# pypl_v1_4.net
KiCad netlist of a schematic drawn in EAGLE
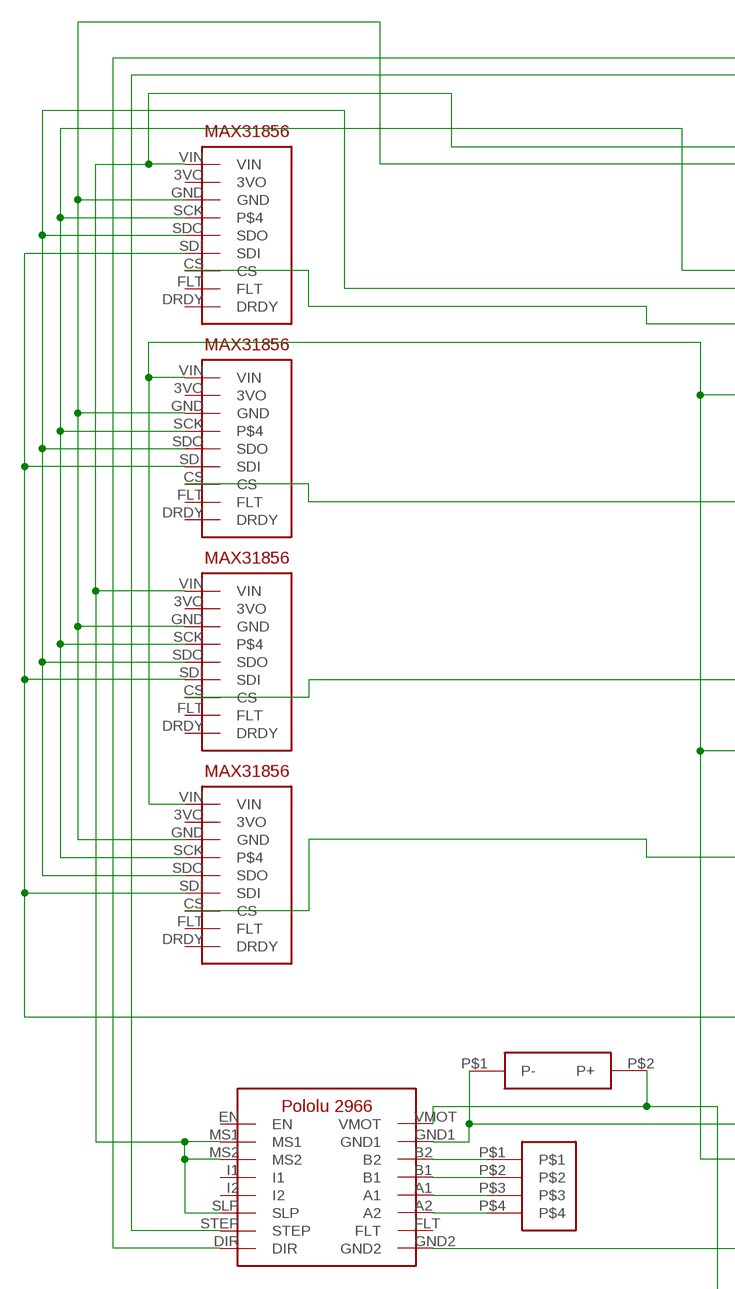
[diagram p0: schematic, sheet 1, part 1 of 2]
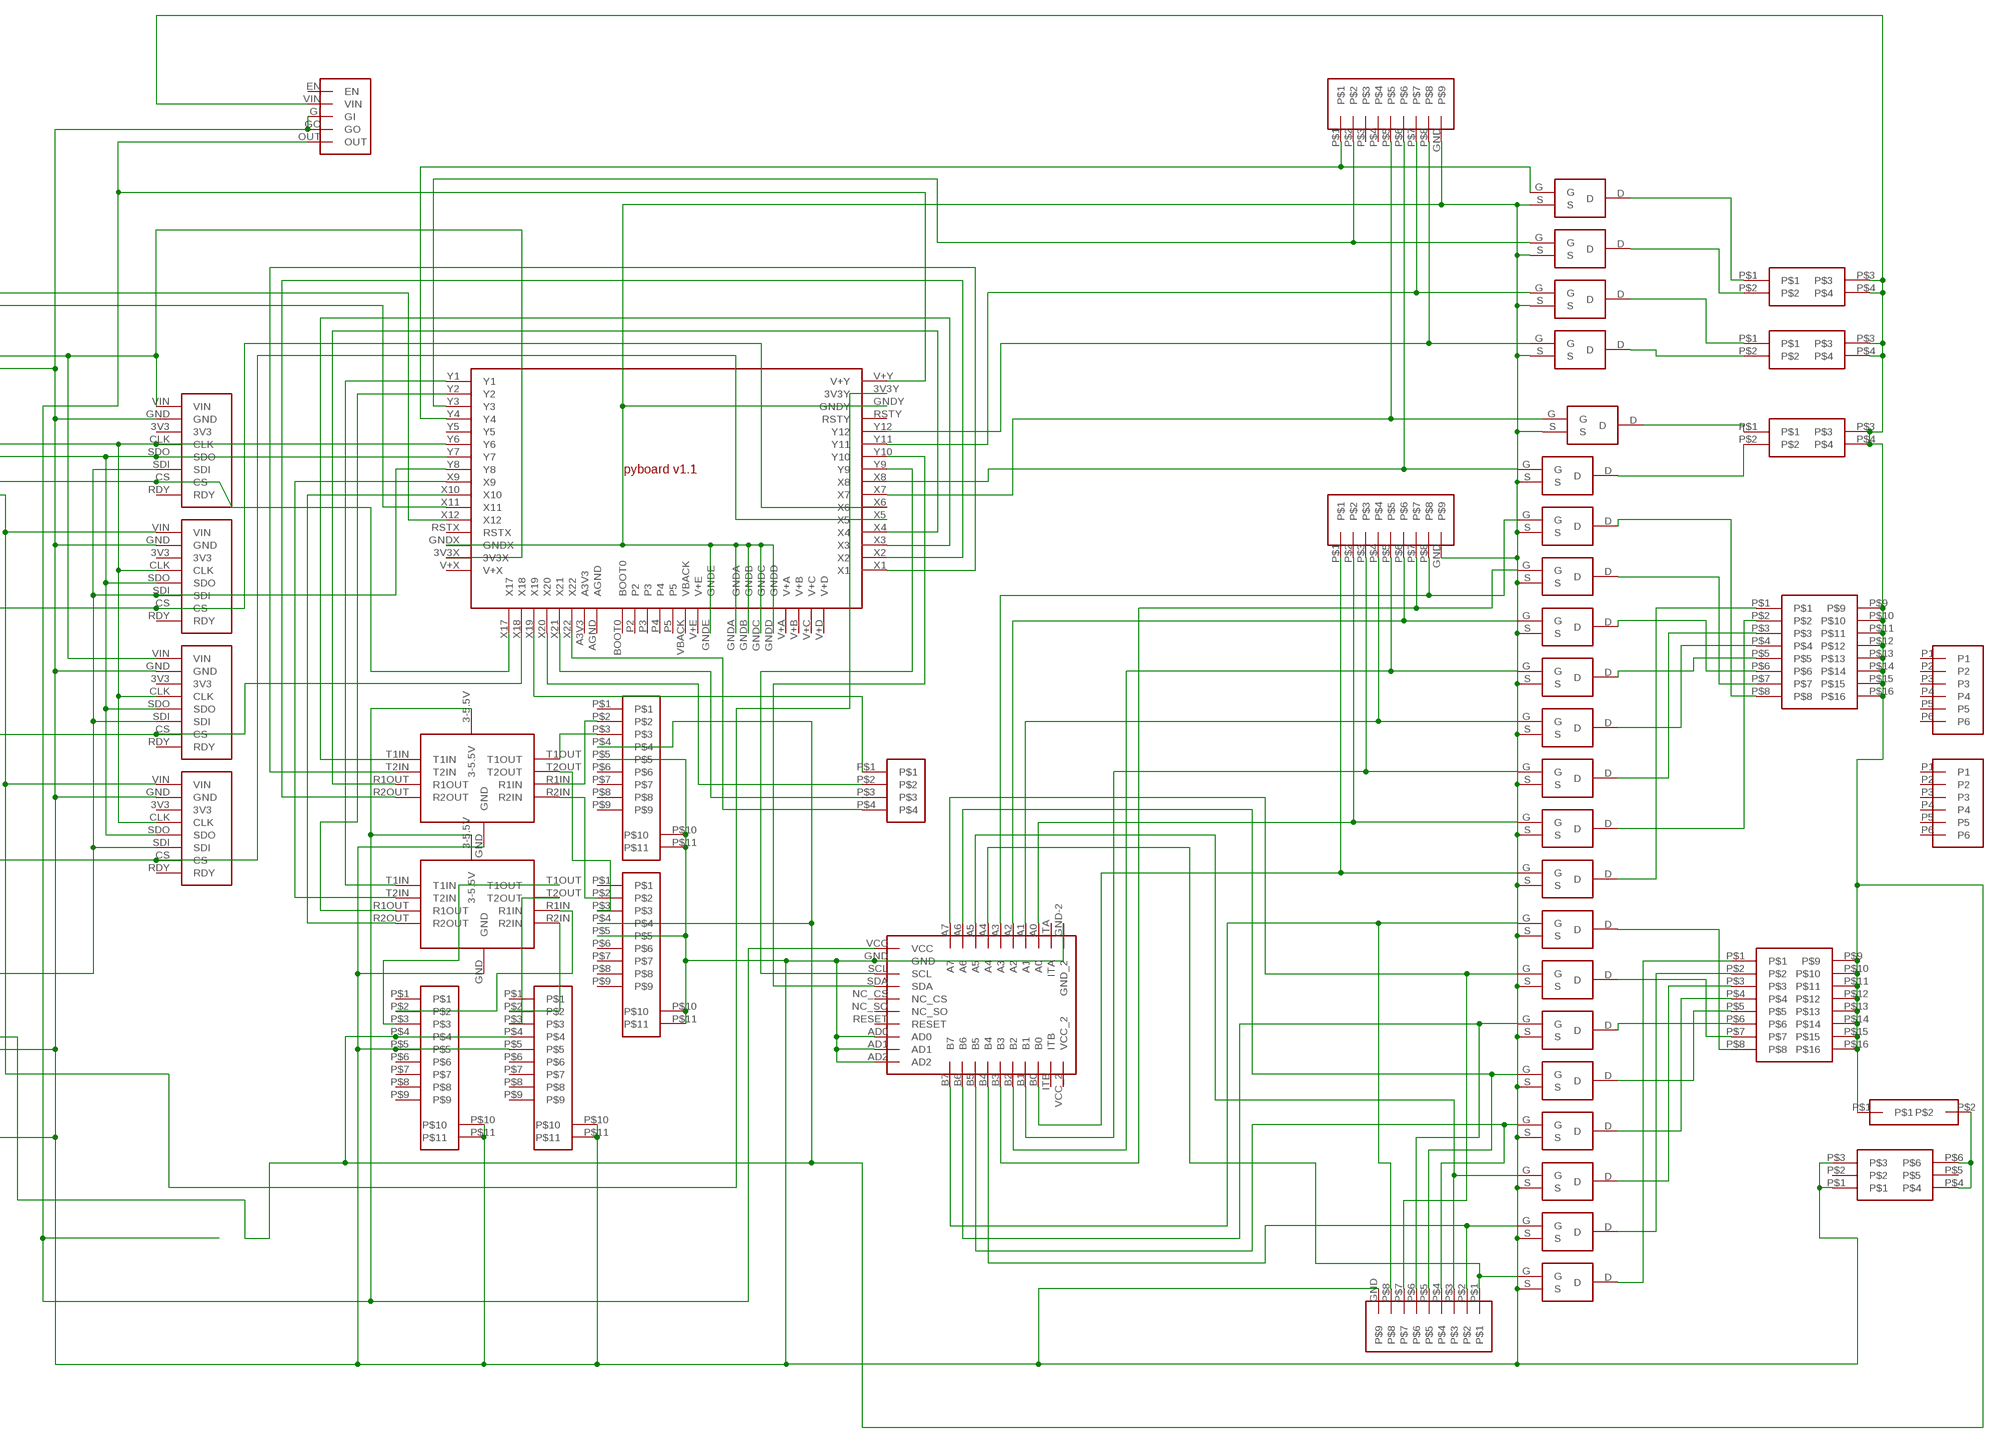
[diagram p1: schematic, sheet 1, part 2 of 2]

(export (version "E")
  (design (tool "Eeschema 10.0.6"))
  (components
    (comp (ref "U$1")
      (value "MAX31865")
      (footprint "eagle-import:MAX31865")
      (libsource (lib "eagle-import") (part "MAX31865"))
    )
    (comp (ref "U$2")
      (value "IRLB8721PBF")
      (footprint "eagle-import:IRLB8721PBF")
      (libsource (lib "eagle-import") (part "IRLB8721PBF"))
    )
    (comp (ref "U$3")
      (value "IRLB8721PBF")
      (footprint "eagle-import:IRLB8721PBF")
      (libsource (lib "eagle-import") (part "IRLB8721PBF"))
    )
    (comp (ref "U$4")
      (value "IRLB8721PBF")
      (footprint "eagle-import:IRLB8721PBF")
      (libsource (lib "eagle-import") (part "IRLB8721PBF"))
    )
    (comp (ref "U$5")
      (value "IRLB8721PBF")
      (footprint "eagle-import:IRLB8721PBF")
      (libsource (lib "eagle-import") (part "IRLB8721PBF"))
    )
    (comp (ref "U$6")
      (value "IRLB8721PBF")
      (footprint "eagle-import:IRLB8721PBF")
      (libsource (lib "eagle-import") (part "IRLB8721PBF"))
    )
    (comp (ref "U$7")
      (value "IRLB8721PBF")
      (footprint "eagle-import:IRLB8721PBF")
      (libsource (lib "eagle-import") (part "IRLB8721PBF"))
    )
    (comp (ref "U$8")
      (value "IRLB8721PBF")
      (footprint "eagle-import:IRLB8721PBF")
      (libsource (lib "eagle-import") (part "IRLB8721PBF"))
    )
    (comp (ref "U$9")
      (value "IRLB8721PBF")
      (footprint "eagle-import:IRLB8721PBF")
      (libsource (lib "eagle-import") (part "IRLB8721PBF"))
    )
    (comp (ref "U$10")
      (value "MCP23017")
      (footprint "eagle-import:MCP23017")
      (libsource (lib "eagle-import") (part "MCP23017"))
    )
    (comp (ref "U$11")
      (value "IRLB8721PBF")
      (footprint "eagle-import:IRLB8721PBF")
      (libsource (lib "eagle-import") (part "IRLB8721PBF"))
    )
    (comp (ref "U$12")
      (value "IRLB8721PBF")
      (footprint "eagle-import:IRLB8721PBF")
      (libsource (lib "eagle-import") (part "IRLB8721PBF"))
    )
    (comp (ref "U$13")
      (value "IRLB8721PBF")
      (footprint "eagle-import:IRLB8721PBF")
      (libsource (lib "eagle-import") (part "IRLB8721PBF"))
    )
    (comp (ref "U$14")
      (value "IRLB8721PBF")
      (footprint "eagle-import:IRLB8721PBF")
      (libsource (lib "eagle-import") (part "IRLB8721PBF"))
    )
    (comp (ref "U$15")
      (value "IRLB8721PBF")
      (footprint "eagle-import:IRLB8721PBF")
      (libsource (lib "eagle-import") (part "IRLB8721PBF"))
    )
    (comp (ref "U$16")
      (value "IRLB8721PBF")
      (footprint "eagle-import:IRLB8721PBF")
      (libsource (lib "eagle-import") (part "IRLB8721PBF"))
    )
    (comp (ref "U$17")
      (value "IRLB8721PBF")
      (footprint "eagle-import:IRLB8721PBF")
      (libsource (lib "eagle-import") (part "IRLB8721PBF"))
    )
    (comp (ref "U$18")
      (value "IRLB8721PBF")
      (footprint "eagle-import:IRLB8721PBF")
      (libsource (lib "eagle-import") (part "IRLB8721PBF"))
    )
    (comp (ref "U$19")
      (value "DSUB-9")
      (footprint "eagle-import:DSUB-9")
      (libsource (lib "eagle-import") (part "DSUB-9"))
    )
    (comp (ref "U$20")
      (value "DSUB-9")
      (footprint "eagle-import:DSUB-9")
      (libsource (lib "eagle-import") (part "DSUB-9"))
    )
    (comp (ref "U$21")
      (value "DSUB-9")
      (footprint "eagle-import:DSUB-9")
      (libsource (lib "eagle-import") (part "DSUB-9"))
    )
    (comp (ref "U$22")
      (value "DSUB-9")
      (footprint "eagle-import:DSUB-9")
      (libsource (lib "eagle-import") (part "DSUB-9"))
    )
    (comp (ref "U$23")
      (value "MAX31865")
      (footprint "eagle-import:MAX31865")
      (libsource (lib "eagle-import") (part "MAX31865"))
    )
    (comp (ref "U$24")
      (value "PYBOARD_V1.1")
      (footprint "eagle-import:PYBOARD_V1.1")
      (libsource (lib "eagle-import") (part "PYBOARD_V1.1"))
    )
    (comp (ref "U$25")
      (value "MAX31865")
      (footprint "eagle-import:MAX31865")
      (libsource (lib "eagle-import") (part "MAX31865"))
    )
    (comp (ref "U$26")
      (value "MAX31865")
      (footprint "eagle-import:MAX31865")
      (libsource (lib "eagle-import") (part "MAX31865"))
    )
    (comp (ref "U$27")
      (value "BORNIER_DUPLEX_X16")
      (footprint "eagle-import:BORNIER_DUPLEX_X16")
      (libsource (lib "eagle-import") (part "BORNIER_DUPLEX_X16"))
    )
    (comp (ref "U$28")
      (value "BORNIER_DUPLEX_X16")
      (footprint "eagle-import:BORNIER_DUPLEX_X16")
      (libsource (lib "eagle-import") (part "BORNIER_DUPLEX_X16"))
    )
    (comp (ref "U$29")
      (value "CAP-GOTRONIC-04936")
      (footprint "eagle-import:CAP-GOTRONIC-04936")
      (libsource (lib "eagle-import") (part "CAP-GOTRONIC-04936"))
    )
    (comp (ref "U$30")
      (value "BORNIER_1X4_2.54")
      (footprint "eagle-import:BORNIER_1X4_2.54")
      (libsource (lib "eagle-import") (part "BORNIER_1X4_2.54"))
    )
    (comp (ref "U$31")
      (value "PORTE-FUSIBLE")
      (footprint "eagle-import:PORTE-FUSIBLE")
      (libsource (lib "eagle-import") (part "PORTE-FUSIBLE"))
    )
    (comp (ref "U$32")
      (value "MP6500-2966")
      (footprint "eagle-import:MP6500-2966")
      (libsource (lib "eagle-import") (part "MP6500-2966"))
    )
    (comp (ref "U$33")
      (value "IRLB8721PBF")
      (footprint "eagle-import:IRLB8721PBF")
      (libsource (lib "eagle-import") (part "IRLB8721PBF"))
    )
    (comp (ref "U$34")
      (value "IRLB8721PBF")
      (footprint "eagle-import:IRLB8721PBF")
      (libsource (lib "eagle-import") (part "IRLB8721PBF"))
    )
    (comp (ref "U$35")
      (value "BORNIER_DUPLEX_X4")
      (footprint "eagle-import:BORNIER_DUPLEX_X4")
      (libsource (lib "eagle-import") (part "BORNIER_DUPLEX_X4"))
    )
    (comp (ref "U$36")
      (value "BOB-1189")
      (footprint "eagle-import:BOB-11189")
      (libsource (lib "eagle-import") (part "BOB-1189"))
    )
    (comp (ref "U$37")
      (value "BOB-1189")
      (footprint "eagle-import:BOB-11189")
      (libsource (lib "eagle-import") (part "BOB-1189"))
    )
    (comp (ref "U$38")
      (value "MOLEX_MINIFT_JR_ANGLED_X6")
      (footprint "eagle-import:MOLEX_MINIFT_JR_ANGLED_X6")
      (libsource (lib "eagle-import") (part "MOLEX_MINIFT_JR_ANGLED_X6"))
    )
    (comp (ref "U$39")
      (value "D24V50F5D24V50F5")
      (footprint "eagle-import:D24V50F5")
      (libsource (lib "eagle-import") (part "D24V50F5D24V50F5"))
    )
    (comp (ref "U$40")
      (value "BORNIER_DUPLEX_X4")
      (footprint "eagle-import:BORNIER_DUPLEX_X4")
      (libsource (lib "eagle-import") (part "BORNIER_DUPLEX_X4"))
    )
    (comp (ref "U$41")
      (value "BORNIER_DUPLEX_X4")
      (footprint "eagle-import:BORNIER_DUPLEX_X4")
      (libsource (lib "eagle-import") (part "BORNIER_DUPLEX_X4"))
    )
    (comp (ref "U$42")
      (value "IRLB8721PBF")
      (footprint "eagle-import:IRLB8721PBF")
      (libsource (lib "eagle-import") (part "IRLB8721PBF"))
    )
    (comp (ref "U$43")
      (value "IRLB8721PBF")
      (footprint "eagle-import:IRLB8721PBF")
      (libsource (lib "eagle-import") (part "IRLB8721PBF"))
    )
    (comp (ref "U$44")
      (value "IRLB8721PBF")
      (footprint "eagle-import:IRLB8721PBF")
      (libsource (lib "eagle-import") (part "IRLB8721PBF"))
    )
    (comp (ref "U$45")
      (value "IRLB8721PBF")
      (footprint "eagle-import:IRLB8721PBF")
      (libsource (lib "eagle-import") (part "IRLB8721PBF"))
    )
    (comp (ref "U$46")
      (value "BORNIER_1X4_2.54")
      (footprint "eagle-import:BORNIER_1X4_2.54")
      (libsource (lib "eagle-import") (part "BORNIER_1X4_2.54"))
    )
    (comp (ref "U$47")
      (value "RESISTOR_BANK_BUSSED_X8")
      (footprint "eagle-import:RESISTOR_BANK_BUSSED_X8")
      (libsource (lib "eagle-import") (part "RESISTOR_BANK_BUSSED_X8"))
    )
    (comp (ref "U$48")
      (value "RESISTOR_BANK_BUSSED_X8")
      (footprint "eagle-import:RESISTOR_BANK_BUSSED_X8")
      (libsource (lib "eagle-import") (part "RESISTOR_BANK_BUSSED_X8"))
    )
    (comp (ref "U$49")
      (value "RESISTOR_BANK_BUSSED_X8")
      (footprint "eagle-import:RESISTOR_BANK_BUSSED_X8")
      (libsource (lib "eagle-import") (part "RESISTOR_BANK_BUSSED_X8"))
    )
    (comp (ref "U$50")
      (value "MAX31856")
      (footprint "eagle-import:MAX31856")
      (libsource (lib "eagle-import") (part "MAX31856"))
    )
    (comp (ref "U$51")
      (value "MAX31856")
      (footprint "eagle-import:MAX31856")
      (libsource (lib "eagle-import") (part "MAX31856"))
    )
    (comp (ref "U$52")
      (value "MAX31856")
      (footprint "eagle-import:MAX31856")
      (libsource (lib "eagle-import") (part "MAX31856"))
    )
    (comp (ref "U$53")
      (value "MAX31856")
      (footprint "eagle-import:MAX31856")
      (libsource (lib "eagle-import") (part "MAX31856"))
    )
    (comp (ref "U$54")
      (value "PINH06")
      (footprint "eagle-import:PINH06")
      (libsource (lib "eagle-import") (part "PINH06"))
    )
    (comp (ref "U$55")
      (value "PINH06")
      (footprint "eagle-import:PINH06")
      (libsource (lib "eagle-import") (part "PINH06"))
    )
  )
  (nets
    (net (code "1") (name "Net-(U$1-PadCS)") (class "Default")
      (node (ref "U$1") (pin "CS") (pinfunction "CS_CS") (pintype "bidirectional"))
      (node (ref "U$24") (pin "X18") (pinfunction "X18_X18") (pintype "bidirectional"))
      (node (ref "U$52") (pin "CS") (pinfunction "CS_CS") (pintype "bidirectional"))
    )
    (net (code "2") (name "Net-(U$1-PadSDI)") (class "Default")
      (node (ref "U$1") (pin "SDI") (pinfunction "SDI_SDI") (pintype "bidirectional"))
      (node (ref "U$23") (pin "SDI") (pinfunction "SDI_SDI") (pintype "bidirectional"))
      (node (ref "U$24") (pin "Y8") (pinfunction "Y8_Y8") (pintype "bidirectional"))
      (node (ref "U$25") (pin "SDI") (pinfunction "SDI_SDI") (pintype "bidirectional"))
      (node (ref "U$26") (pin "SDI") (pinfunction "SDI_SDI") (pintype "bidirectional"))
      (node (ref "U$50") (pin "SDI") (pinfunction "SDI_SDI") (pintype "bidirectional"))
      (node (ref "U$51") (pin "SDI") (pinfunction "SDI_SDI") (pintype "bidirectional"))
      (node (ref "U$52") (pin "SDI") (pinfunction "SDI_SDI") (pintype "bidirectional"))
      (node (ref "U$53") (pin "SDI") (pinfunction "SDI_SDI") (pintype "bidirectional"))
    )
    (net (code "3") (name "Net-(U$1-PadSDO)") (class "Default")
      (node (ref "U$1") (pin "SDO") (pinfunction "SDO_SDO") (pintype "bidirectional"))
      (node (ref "U$23") (pin "SDO") (pinfunction "SDO_SDO") (pintype "bidirectional"))
      (node (ref "U$24") (pin "Y7") (pinfunction "Y7_Y7") (pintype "bidirectional"))
      (node (ref "U$25") (pin "SDO") (pinfunction "SDO_SDO") (pintype "bidirectional"))
      (node (ref "U$26") (pin "SDO") (pinfunction "SDO_SDO") (pintype "bidirectional"))
      (node (ref "U$50") (pin "SDO") (pinfunction "SDO_SDO") (pintype "bidirectional"))
      (node (ref "U$51") (pin "SDO") (pinfunction "SDO_SDO") (pintype "bidirectional"))
      (node (ref "U$52") (pin "SDO") (pinfunction "SDO_SDO") (pintype "bidirectional"))
      (node (ref "U$53") (pin "SDO") (pinfunction "SDO_SDO") (pintype "bidirectional"))
    )
    (net (code "4") (name "Net-(U$1-PadVIN)") (class "Default")
      (node (ref "U$1") (pin "VIN") (pinfunction "VIN_VIN") (pintype "bidirectional"))
      (node (ref "U$24") (pin "3V3X") (pinfunction "3V3X_3V3X") (pintype "bidirectional"))
      (node (ref "U$25") (pin "VIN") (pinfunction "VIN_VIN") (pintype "bidirectional"))
      (node (ref "U$32") (pin "MS1") (pinfunction "MS1_MS1") (pintype "bidirectional"))
      (node (ref "U$32") (pin "MS2") (pinfunction "MS2_MS2") (pintype "bidirectional"))
      (node (ref "U$32") (pin "SLP") (pinfunction "SLP_SLP") (pintype "bidirectional"))
      (node (ref "U$50") (pin "VIN") (pinfunction "VIN_VIN") (pintype "bidirectional"))
      (node (ref "U$52") (pin "VIN") (pinfunction "VIN_VIN") (pintype "bidirectional"))
    )
    (net (code "5") (name "Net-(U$2-PadD)") (class "Default")
      (node (ref "U$2") (pin "D") (pinfunction "D_D") (pintype "bidirectional"))
      (node (ref "U$28") (pin "P$3") (pinfunction "P$3_P$3") (pintype "bidirectional"))
    )
    (net (code "6") (name "Net-(U$10-GND_2)") (class "Default")
      (node (ref "U$1") (pin "GND") (pinfunction "GND_GND") (pintype "bidirectional"))
      (node (ref "U$10") (pin "AD0") (pinfunction "AD0_AD0") (pintype "bidirectional"))
      (node (ref "U$10") (pin "AD1") (pinfunction "AD1_AD1") (pintype "bidirectional"))
      (node (ref "U$10") (pin "AD2") (pinfunction "AD2_AD2") (pintype "bidirectional"))
      (node (ref "U$10") (pin "GND") (pinfunction "GND_GND") (pintype "bidirectional"))
      (node (ref "U$10") (pin "GND-2") (pinfunction "GND_2_GND-2") (pintype "bidirectional"))
      (node (ref "U$11") (pin "S") (pinfunction "S_S") (pintype "bidirectional"))
      (node (ref "U$12") (pin "S") (pinfunction "S_S") (pintype "bidirectional"))
      (node (ref "U$13") (pin "S") (pinfunction "S_S") (pintype "bidirectional"))
      (node (ref "U$14") (pin "S") (pinfunction "S_S") (pintype "bidirectional"))
      (node (ref "U$15") (pin "S") (pinfunction "S_S") (pintype "bidirectional"))
      (node (ref "U$16") (pin "S") (pinfunction "S_S") (pintype "bidirectional"))
      (node (ref "U$17") (pin "S") (pinfunction "S_S") (pintype "bidirectional"))
      (node (ref "U$18") (pin "S") (pinfunction "S_S") (pintype "bidirectional"))
      (node (ref "U$19") (pin "P$10") (pinfunction "P$10_P$10") (pintype "bidirectional"))
      (node (ref "U$19") (pin "P$11") (pinfunction "P$11_P$11") (pintype "bidirectional"))
      (node (ref "U$19") (pin "P$5") (pinfunction "P$5_P$5") (pintype "bidirectional"))
      (node (ref "U$2") (pin "S") (pinfunction "S_S") (pintype "bidirectional"))
      (node (ref "U$20") (pin "P$10") (pinfunction "P$10_P$10") (pintype "bidirectional"))
      (node (ref "U$20") (pin "P$11") (pinfunction "P$11_P$11") (pintype "bidirectional"))
      (node (ref "U$20") (pin "P$5") (pinfunction "P$5_P$5") (pintype "bidirectional"))
      (node (ref "U$21") (pin "P$10") (pinfunction "P$10_P$10") (pintype "bidirectional"))
      (node (ref "U$21") (pin "P$11") (pinfunction "P$11_P$11") (pintype "bidirectional"))
      (node (ref "U$21") (pin "P$5") (pinfunction "P$5_P$5") (pintype "bidirectional"))
      (node (ref "U$22") (pin "P$10") (pinfunction "P$10_P$10") (pintype "bidirectional"))
      (node (ref "U$22") (pin "P$11") (pinfunction "P$11_P$11") (pintype "bidirectional"))
      (node (ref "U$22") (pin "P$5") (pinfunction "P$5_P$5") (pintype "bidirectional"))
      (node (ref "U$23") (pin "GND") (pinfunction "GND_GND") (pintype "bidirectional"))
      (node (ref "U$24") (pin "GNDA") (pinfunction "GNDA_GNDA") (pintype "bidirectional"))
      (node (ref "U$24") (pin "GNDB") (pinfunction "GNDB_GNDB") (pintype "bidirectional"))
      (node (ref "U$24") (pin "GNDC") (pinfunction "GNDC_GNDC") (pintype "bidirectional"))
      (node (ref "U$24") (pin "GNDD") (pinfunction "GNDD_GNDD") (pintype "bidirectional"))
      (node (ref "U$24") (pin "GNDE") (pinfunction "GNDE_GNDE") (pintype "bidirectional"))
      (node (ref "U$24") (pin "GNDX") (pinfunction "GNDX_GNDX") (pintype "bidirectional"))
      (node (ref "U$24") (pin "GNDY") (pinfunction "GNDY_GNDY") (pintype "bidirectional"))
      (node (ref "U$25") (pin "GND") (pinfunction "GND_GND") (pintype "bidirectional"))
      (node (ref "U$26") (pin "GND") (pinfunction "GND_GND") (pintype "bidirectional"))
      (node (ref "U$29") (pin "P$1") (pinfunction "P-_P$1") (pintype "bidirectional"))
      (node (ref "U$3") (pin "S") (pinfunction "S_S") (pintype "bidirectional"))
      (node (ref "U$32") (pin "GND1") (pinfunction "GND1_GND1") (pintype "bidirectional"))
      (node (ref "U$32") (pin "GND2") (pinfunction "GND2_GND2") (pintype "bidirectional"))
      (node (ref "U$33") (pin "S") (pinfunction "S_S") (pintype "bidirectional"))
      (node (ref "U$34") (pin "S") (pinfunction "S_S") (pintype "bidirectional"))
      (node (ref "U$36") (pin "GND") (pinfunction "GND_GND") (pintype "bidirectional"))
      (node (ref "U$37") (pin "GND") (pinfunction "GND_GND") (pintype "bidirectional"))
      (node (ref "U$38") (pin "P$1") (pinfunction "P$1_P$1") (pintype "bidirectional"))
      (node (ref "U$38") (pin "P$3") (pinfunction "P$3_P$3") (pintype "bidirectional"))
      (node (ref "U$39") (pin "GI") (pinfunction "GI_GI") (pintype "bidirectional"))
      (node (ref "U$39") (pin "GO") (pinfunction "GO_GO") (pintype "bidirectional"))
      (node (ref "U$4") (pin "S") (pinfunction "S_S") (pintype "bidirectional"))
      (node (ref "U$42") (pin "S") (pinfunction "S_S") (pintype "bidirectional"))
      (node (ref "U$43") (pin "S") (pinfunction "S_S") (pintype "bidirectional"))
      (node (ref "U$44") (pin "S") (pinfunction "S_S") (pintype "bidirectional"))
      (node (ref "U$45") (pin "S") (pinfunction "S_S") (pintype "bidirectional"))
      (node (ref "U$47") (pin "GND") (pinfunction "P$9_GND") (pintype "bidirectional"))
      (node (ref "U$48") (pin "GND") (pinfunction "P$9_GND") (pintype "bidirectional"))
      (node (ref "U$49") (pin "GND") (pinfunction "P$9_GND") (pintype "bidirectional"))
      (node (ref "U$5") (pin "S") (pinfunction "S_S") (pintype "bidirectional"))
      (node (ref "U$50") (pin "GND") (pinfunction "GND_GND") (pintype "bidirectional"))
      (node (ref "U$51") (pin "GND") (pinfunction "GND_GND") (pintype "bidirectional"))
      (node (ref "U$52") (pin "GND") (pinfunction "GND_GND") (pintype "bidirectional"))
      (node (ref "U$53") (pin "GND") (pinfunction "GND_GND") (pintype "bidirectional"))
      (node (ref "U$6") (pin "S") (pinfunction "S_S") (pintype "bidirectional"))
      (node (ref "U$7") (pin "S") (pinfunction "S_S") (pintype "bidirectional"))
      (node (ref "U$8") (pin "S") (pinfunction "S_S") (pintype "bidirectional"))
      (node (ref "U$9") (pin "S") (pinfunction "S_S") (pintype "bidirectional"))
    )
    (net (code "7") (name "Net-(U$10-PadA0)") (class "Default")
      (node (ref "U$10") (pin "A0") (pinfunction "A0_A0") (pintype "bidirectional"))
      (node (ref "U$48") (pin "P$2") (pinfunction "P$2_P$2") (pintype "bidirectional"))
      (node (ref "U$8") (pin "G") (pinfunction "G_G") (pintype "bidirectional"))
    )
    (net (code "8") (name "Net-(U$10-PadA1)") (class "Default")
      (node (ref "U$10") (pin "A1") (pinfunction "A1_A1") (pintype "bidirectional"))
      (node (ref "U$3") (pin "G") (pinfunction "G_G") (pintype "bidirectional"))
      (node (ref "U$48") (pin "P$4") (pinfunction "P$4_P$4") (pintype "bidirectional"))
    )
    (net (code "9") (name "Net-(U$10-PadA2)") (class "Default")
      (node (ref "U$10") (pin "A2") (pinfunction "A2_A2") (pintype "bidirectional"))
      (node (ref "U$48") (pin "P$6") (pinfunction "P$6_P$6") (pintype "bidirectional"))
      (node (ref "U$5") (pin "G") (pinfunction "G_G") (pintype "bidirectional"))
    )
    (net (code "10") (name "Net-(U$10-PadA3)") (class "Default")
      (node (ref "U$10") (pin "A3") (pinfunction "A3_A3") (pintype "bidirectional"))
      (node (ref "U$48") (pin "P$8") (pinfunction "P$8_P$8") (pintype "bidirectional"))
      (node (ref "U$7") (pin "G") (pinfunction "G_G") (pintype "bidirectional"))
    )
    (net (code "11") (name "Net-(U$10-PadA4)") (class "Default")
      (node (ref "U$10") (pin "A4") (pinfunction "A4_A4") (pintype "bidirectional"))
      (node (ref "U$18") (pin "G") (pinfunction "G_G") (pintype "bidirectional"))
      (node (ref "U$47") (pin "P$1") (pinfunction "P$1_P$1") (pintype "bidirectional"))
    )
    (net (code "12") (name "Net-(U$10-PadA5)") (class "Default")
      (node (ref "U$10") (pin "A5") (pinfunction "A5_A5") (pintype "bidirectional"))
      (node (ref "U$11") (pin "G") (pinfunction "G_G") (pintype "bidirectional"))
      (node (ref "U$47") (pin "P$3") (pinfunction "P$3_P$3") (pintype "bidirectional"))
    )
    (net (code "13") (name "Net-(U$10-PadA6)") (class "Default")
      (node (ref "U$10") (pin "A6") (pinfunction "A6_A6") (pintype "bidirectional"))
      (node (ref "U$13") (pin "G") (pinfunction "G_G") (pintype "bidirectional"))
      (node (ref "U$47") (pin "P$5") (pinfunction "P$5_P$5") (pintype "bidirectional"))
    )
    (net (code "14") (name "Net-(U$10-PadA7)") (class "Default")
      (node (ref "U$10") (pin "A7") (pinfunction "A7_A7") (pintype "bidirectional"))
      (node (ref "U$15") (pin "G") (pinfunction "G_G") (pintype "bidirectional"))
      (node (ref "U$47") (pin "P$7") (pinfunction "P$7_P$7") (pintype "bidirectional"))
    )
    (net (code "15") (name "Net-(U$10-PadB0)") (class "Default")
      (node (ref "U$10") (pin "B0") (pinfunction "B0_B0") (pintype "bidirectional"))
      (node (ref "U$48") (pin "P$1") (pinfunction "P$1_P$1") (pintype "bidirectional"))
      (node (ref "U$9") (pin "G") (pinfunction "G_G") (pintype "bidirectional"))
    )
    (net (code "16") (name "Net-(U$10-PadB1)") (class "Default")
      (node (ref "U$10") (pin "B1") (pinfunction "B1_B1") (pintype "bidirectional"))
      (node (ref "U$2") (pin "G") (pinfunction "G_G") (pintype "bidirectional"))
      (node (ref "U$48") (pin "P$3") (pinfunction "P$3_P$3") (pintype "bidirectional"))
    )
    (net (code "17") (name "Net-(U$10-PadB2)") (class "Default")
      (node (ref "U$10") (pin "B2") (pinfunction "B2_B2") (pintype "bidirectional"))
      (node (ref "U$4") (pin "G") (pinfunction "G_G") (pintype "bidirectional"))
      (node (ref "U$48") (pin "P$5") (pinfunction "P$5_P$5") (pintype "bidirectional"))
    )
    (net (code "18") (name "Net-(U$10-PadB3)") (class "Default")
      (node (ref "U$10") (pin "B3") (pinfunction "B3_B3") (pintype "bidirectional"))
      (node (ref "U$48") (pin "P$7") (pinfunction "P$7_P$7") (pintype "bidirectional"))
      (node (ref "U$6") (pin "G") (pinfunction "G_G") (pintype "bidirectional"))
    )
    (net (code "19") (name "Net-(U$10-PadB4)") (class "Default")
      (node (ref "U$10") (pin "B4") (pinfunction "B4_B4") (pintype "bidirectional"))
      (node (ref "U$17") (pin "G") (pinfunction "G_G") (pintype "bidirectional"))
      (node (ref "U$47") (pin "P$2") (pinfunction "P$2_P$2") (pintype "bidirectional"))
    )
    (net (code "20") (name "Net-(U$10-PadB5)") (class "Default")
      (node (ref "U$10") (pin "B5") (pinfunction "B5_B5") (pintype "bidirectional"))
      (node (ref "U$12") (pin "G") (pinfunction "G_G") (pintype "bidirectional"))
      (node (ref "U$47") (pin "P$4") (pinfunction "P$4_P$4") (pintype "bidirectional"))
    )
    (net (code "21") (name "Net-(U$10-PadB6)") (class "Default")
      (node (ref "U$10") (pin "B6") (pinfunction "B6_B6") (pintype "bidirectional"))
      (node (ref "U$14") (pin "G") (pinfunction "G_G") (pintype "bidirectional"))
      (node (ref "U$47") (pin "P$6") (pinfunction "P$6_P$6") (pintype "bidirectional"))
    )
    (net (code "22") (name "Net-(U$10-PadB7)") (class "Default")
      (node (ref "U$10") (pin "B7") (pinfunction "B7_B7") (pintype "bidirectional"))
      (node (ref "U$16") (pin "G") (pinfunction "G_G") (pintype "bidirectional"))
      (node (ref "U$47") (pin "P$8") (pinfunction "P$8_P$8") (pintype "bidirectional"))
    )
    (net (code "23") (name "Net-(U$10-PadSCL)") (class "Default")
      (node (ref "U$10") (pin "SCL") (pinfunction "SCL_SCL") (pintype "bidirectional"))
      (node (ref "U$24") (pin "Y9") (pinfunction "Y9_Y9") (pintype "bidirectional"))
    )
    (net (code "24") (name "Net-(U$10-PadSDA)") (class "Default")
      (node (ref "U$10") (pin "SDA") (pinfunction "SDA_SDA") (pintype "bidirectional"))
      (node (ref "U$24") (pin "Y10") (pinfunction "Y10_Y10") (pintype "bidirectional"))
    )
    (net (code "25") (name "Net-(U$10-PadVCC)") (class "Default")
      (node (ref "U$10") (pin "VCC") (pinfunction "VCC_VCC") (pintype "bidirectional"))
      (node (ref "U$24") (pin "V+Y") (pinfunction "V+Y_V+Y") (pintype "bidirectional"))
      (node (ref "U$36") (pin "3-5.5V") (pinfunction "3-5.5V_3-5.5V") (pintype "bidirectional"))
      (node (ref "U$37") (pin "3-5.5V") (pinfunction "3-5.5V_3-5.5V") (pintype "bidirectional"))
      (node (ref "U$39") (pin "OUT") (pinfunction "OUT_OUT") (pintype "bidirectional"))
    )
    (net (code "26") (name "Net-(U$11-PadD)") (class "Default")
      (node (ref "U$11") (pin "D") (pinfunction "D_D") (pintype "bidirectional"))
      (node (ref "U$27") (pin "P$3") (pinfunction "P$3_P$3") (pintype "bidirectional"))
    )
    (net (code "27") (name "Net-(U$12-PadD)") (class "Default")
      (node (ref "U$12") (pin "D") (pinfunction "D_D") (pintype "bidirectional"))
      (node (ref "U$27") (pin "P$4") (pinfunction "P$4_P$4") (pintype "bidirectional"))
    )
    (net (code "28") (name "Net-(U$13-PadD)") (class "Default")
      (node (ref "U$13") (pin "D") (pinfunction "D_D") (pintype "bidirectional"))
      (node (ref "U$27") (pin "P$5") (pinfunction "P$5_P$5") (pintype "bidirectional"))
    )
    (net (code "29") (name "Net-(U$14-PadD)") (class "Default")
      (node (ref "U$14") (pin "D") (pinfunction "D_D") (pintype "bidirectional"))
      (node (ref "U$27") (pin "P$6") (pinfunction "P$6_P$6") (pintype "bidirectional"))
    )
    (net (code "30") (name "Net-(U$15-PadD)") (class "Default")
      (node (ref "U$15") (pin "D") (pinfunction "D_D") (pintype "bidirectional"))
      (node (ref "U$27") (pin "P$7") (pinfunction "P$7_P$7") (pintype "bidirectional"))
    )
    (net (code "31") (name "Net-(U$16-PadD)") (class "Default")
      (node (ref "U$16") (pin "D") (pinfunction "D_D") (pintype "bidirectional"))
      (node (ref "U$27") (pin "P$8") (pinfunction "P$8_P$8") (pintype "bidirectional"))
    )
    (net (code "32") (name "Net-(U$17-PadD)") (class "Default")
      (node (ref "U$17") (pin "D") (pinfunction "D_D") (pintype "bidirectional"))
      (node (ref "U$27") (pin "P$2") (pinfunction "P$2_P$2") (pintype "bidirectional"))
    )
    (net (code "33") (name "Net-(U$18-PadD)") (class "Default")
      (node (ref "U$18") (pin "D") (pinfunction "D_D") (pintype "bidirectional"))
      (node (ref "U$27") (pin "P$1") (pinfunction "P$1_P$1") (pintype "bidirectional"))
    )
    (net (code "34") (name "Net-(U$19-PadP$2)") (class "Default")
      (node (ref "U$19") (pin "P$2") (pinfunction "P$2_P$2") (pintype "bidirectional"))
      (node (ref "U$36") (pin "R1IN") (pinfunction "R1IN_R1IN") (pintype "bidirectional"))
    )
    (net (code "35") (name "Net-(U$19-PadP$3)") (class "Default")
      (node (ref "U$19") (pin "P$3") (pinfunction "P$3_P$3") (pintype "bidirectional"))
      (node (ref "U$36") (pin "T1OUT") (pinfunction "T1OUT_T1OUT") (pintype "bidirectional"))
    )
    (net (code "36") (name "Net-(U$20-PadP$2)") (class "Default")
      (node (ref "U$20") (pin "P$2") (pinfunction "P$2_P$2") (pintype "bidirectional"))
      (node (ref "U$36") (pin "R2IN") (pinfunction "R2IN_R2IN") (pintype "bidirectional"))
    )
    (net (code "37") (name "Net-(U$20-PadP$3)") (class "Default")
      (node (ref "U$20") (pin "P$3") (pinfunction "P$3_P$3") (pintype "bidirectional"))
      (node (ref "U$36") (pin "T2OUT") (pinfunction "T2OUT_T2OUT") (pintype "bidirectional"))
    )
    (net (code "38") (name "Net-(U$21-PadP$2)") (class "Default")
      (node (ref "U$21") (pin "P$2") (pinfunction "P$2_P$2") (pintype "bidirectional"))
      (node (ref "U$37") (pin "R2IN") (pinfunction "R2IN_R2IN") (pintype "bidirectional"))
    )
    (net (code "39") (name "Net-(U$21-PadP$3)") (class "Default")
      (node (ref "U$21") (pin "P$3") (pinfunction "P$3_P$3") (pintype "bidirectional"))
      (node (ref "U$37") (pin "T2OUT") (pinfunction "T2OUT_T2OUT") (pintype "bidirectional"))
    )
    (net (code "40") (name "Net-(U$22-PadP$2)") (class "Default")
      (node (ref "U$22") (pin "P$2") (pinfunction "P$2_P$2") (pintype "bidirectional"))
      (node (ref "U$37") (pin "R1IN") (pinfunction "R1IN_R1IN") (pintype "bidirectional"))
    )
    (net (code "41") (name "Net-(U$22-PadP$3)") (class "Default")
      (node (ref "U$22") (pin "P$3") (pinfunction "P$3_P$3") (pintype "bidirectional"))
      (node (ref "U$37") (pin "T1OUT") (pinfunction "T1OUT_T1OUT") (pintype "bidirectional"))
    )
    (net (code "42") (name "Net-(U$23-PadCS)") (class "Default")
      (node (ref "U$23") (pin "CS") (pinfunction "CS_CS") (pintype "bidirectional"))
      (node (ref "U$24") (pin "X5") (pinfunction "X5_X5") (pintype "bidirectional"))
      (node (ref "U$53") (pin "CS") (pinfunction "CS_CS") (pintype "bidirectional"))
    )
    (net (code "43") (name "Net-(U$23-PadVIN)") (class "Default")
      (node (ref "U$23") (pin "VIN") (pinfunction "VIN_VIN") (pintype "bidirectional"))
      (node (ref "U$24") (pin "3V3Y") (pinfunction "3V3Y_3V3Y") (pintype "bidirectional"))
      (node (ref "U$26") (pin "VIN") (pinfunction "VIN_VIN") (pintype "bidirectional"))
      (node (ref "U$51") (pin "VIN") (pinfunction "VIN_VIN") (pintype "bidirectional"))
      (node (ref "U$53") (pin "VIN") (pinfunction "VIN_VIN") (pintype "bidirectional"))
    )
    (net (code "44") (name "Net-(U$24-PadX1)") (class "Default")
      (node (ref "U$24") (pin "X1") (pinfunction "X1_X1") (pintype "bidirectional"))
      (node (ref "U$36") (pin "T2IN") (pinfunction "T2IN_T2IN") (pintype "bidirectional"))
    )
    (net (code "45") (name "Net-(U$24-PadX2)") (class "Default")
      (node (ref "U$24") (pin "X2") (pinfunction "X2_X2") (pintype "bidirectional"))
      (node (ref "U$36") (pin "R2OUT") (pinfunction "R2OUT_R2OUT") (pintype "bidirectional"))
    )
    (net (code "46") (name "Net-(U$24-PadX3)") (class "Default")
      (node (ref "U$24") (pin "X3") (pinfunction "X3_X3") (pintype "bidirectional"))
      (node (ref "U$36") (pin "T1IN") (pinfunction "T1IN_T1IN") (pintype "bidirectional"))
    )
    (net (code "47") (name "Net-(U$24-PadX4)") (class "Default")
      (node (ref "U$24") (pin "X4") (pinfunction "X4_X4") (pintype "bidirectional"))
      (node (ref "U$36") (pin "R1OUT") (pinfunction "R1OUT_R1OUT") (pintype "bidirectional"))
    )
    (net (code "48") (name "Net-(U$24-PadX6)") (class "Default")
      (node (ref "U$24") (pin "X6") (pinfunction "X6_X6") (pintype "bidirectional"))
      (node (ref "U$26") (pin "CS") (pinfunction "CS_CS") (pintype "bidirectional"))
      (node (ref "U$51") (pin "CS") (pinfunction "CS_CS") (pintype "bidirectional"))
    )
    (net (code "49") (name "Net-(U$24-PadX7)") (class "Default")
      (node (ref "U$24") (pin "X7") (pinfunction "X7_X7") (pintype "bidirectional"))
      (node (ref "U$34") (pin "G") (pinfunction "G_G") (pintype "bidirectional"))
      (node (ref "U$49") (pin "P$5") (pinfunction "P$5_P$5") (pintype "bidirectional"))
    )
    (net (code "50") (name "Net-(U$24-PadX8)") (class "Default")
      (node (ref "U$24") (pin "X8") (pinfunction "X8_X8") (pintype "bidirectional"))
      (node (ref "U$33") (pin "G") (pinfunction "G_G") (pintype "bidirectional"))
      (node (ref "U$49") (pin "P$6") (pinfunction "P$6_P$6") (pintype "bidirectional"))
    )
    (net (code "51") (name "Net-(U$24-PadX9)") (class "Default")
      (node (ref "U$24") (pin "X9") (pinfunction "X9_X9") (pintype "bidirectional"))
      (node (ref "U$37") (pin "T2IN") (pinfunction "T2IN_T2IN") (pintype "bidirectional"))
    )
    (net (code "52") (name "Net-(U$24-PadX10)") (class "Default")
      (node (ref "U$24") (pin "X10") (pinfunction "X10_X10") (pintype "bidirectional"))
      (node (ref "U$37") (pin "R2OUT") (pinfunction "R2OUT_R2OUT") (pintype "bidirectional"))
    )
    (net (code "53") (name "Net-(U$24-PadX11)") (class "Default")
      (node (ref "U$24") (pin "X11") (pinfunction "X11_X11") (pintype "bidirectional"))
      (node (ref "U$32") (pin "STEP") (pinfunction "STEP_STEP") (pintype "bidirectional"))
    )
    (net (code "54") (name "Net-(U$24-PadX12)") (class "Default")
      (node (ref "U$24") (pin "X12") (pinfunction "X12_X12") (pintype "bidirectional"))
      (node (ref "U$32") (pin "DIR") (pinfunction "DIR_DIR") (pintype "bidirectional"))
    )
    (net (code "55") (name "Net-(U$24-PadX17)") (class "Default")
      (node (ref "U$24") (pin "X17") (pinfunction "X17_X17") (pintype "bidirectional"))
      (node (ref "U$25") (pin "CS") (pinfunction "CS_CS") (pintype "bidirectional"))
      (node (ref "U$50") (pin "CS") (pinfunction "CS_CS") (pintype "bidirectional"))
    )
    (net (code "56") (name "Net-(U$24-PadX19)") (class "Default")
      (node (ref "U$24") (pin "X19") (pinfunction "X19_X19") (pintype "bidirectional"))
      (node (ref "U$46") (pin "P$1") (pinfunction "P$1_P$1") (pintype "bidirectional"))
    )
    (net (code "57") (name "Net-(U$24-PadX20)") (class "Default")
      (node (ref "U$24") (pin "X20") (pinfunction "X20_X20") (pintype "bidirectional"))
      (node (ref "U$46") (pin "P$2") (pinfunction "P$2_P$2") (pintype "bidirectional"))
    )
    (net (code "58") (name "Net-(U$24-PadX21)") (class "Default")
      (node (ref "U$24") (pin "X21") (pinfunction "X21_X21") (pintype "bidirectional"))
      (node (ref "U$46") (pin "P$3") (pinfunction "P$3_P$3") (pintype "bidirectional"))
    )
    (net (code "59") (name "Net-(U$24-PadX22)") (class "Default")
      (node (ref "U$24") (pin "X22") (pinfunction "X22_X22") (pintype "bidirectional"))
      (node (ref "U$46") (pin "P$4") (pinfunction "P$4_P$4") (pintype "bidirectional"))
    )
    (net (code "60") (name "Net-(U$24-PadY1)") (class "Default")
      (node (ref "U$24") (pin "Y1") (pinfunction "Y1_Y1") (pintype "bidirectional"))
      (node (ref "U$37") (pin "T1IN") (pinfunction "T1IN_T1IN") (pintype "bidirectional"))
    )
    (net (code "61") (name "Net-(U$24-PadY2)") (class "Default")
      (node (ref "U$24") (pin "Y2") (pinfunction "Y2_Y2") (pintype "bidirectional"))
      (node (ref "U$37") (pin "R1OUT") (pinfunction "R1OUT_R1OUT") (pintype "bidirectional"))
    )
    (net (code "62") (name "Net-(U$24-PadY3)") (class "Default")
      (node (ref "U$24") (pin "Y3") (pinfunction "Y3_Y3") (pintype "bidirectional"))
      (node (ref "U$44") (pin "G") (pinfunction "G_G") (pintype "bidirectional"))
      (node (ref "U$49") (pin "P$2") (pinfunction "P$2_P$2") (pintype "bidirectional"))
    )
    (net (code "63") (name "Net-(U$24-PadY4)") (class "Default")
      (node (ref "U$24") (pin "Y4") (pinfunction "Y4_Y4") (pintype "bidirectional"))
      (node (ref "U$45") (pin "G") (pinfunction "G_G") (pintype "bidirectional"))
      (node (ref "U$49") (pin "P$1") (pinfunction "P$1_P$1") (pintype "bidirectional"))
    )
    (net (code "64") (name "Net-(U$24-PadY11)") (class "Default")
      (node (ref "U$24") (pin "Y11") (pinfunction "Y11_Y11") (pintype "bidirectional"))
      (node (ref "U$43") (pin "G") (pinfunction "G_G") (pintype "bidirectional"))
      (node (ref "U$49") (pin "P$7") (pinfunction "P$7_P$7") (pintype "bidirectional"))
    )
    (net (code "65") (name "Net-(U$24-PadY12)") (class "Default")
      (node (ref "U$24") (pin "Y12") (pinfunction "Y12_Y12") (pintype "bidirectional"))
      (node (ref "U$42") (pin "G") (pinfunction "G_G") (pintype "bidirectional"))
      (node (ref "U$49") (pin "P$8") (pinfunction "P$8_P$8") (pintype "bidirectional"))
    )
    (net (code "66") (name "Net-(U$28-PadP$1)") (class "Default")
      (node (ref "U$28") (pin "P$1") (pinfunction "P$1_P$1") (pintype "bidirectional"))
      (node (ref "U$9") (pin "D") (pinfunction "D_D") (pintype "bidirectional"))
    )
    (net (code "67") (name "Net-(U$28-PadP$2)") (class "Default")
      (node (ref "U$28") (pin "P$2") (pinfunction "P$2_P$2") (pintype "bidirectional"))
      (node (ref "U$8") (pin "D") (pinfunction "D_D") (pintype "bidirectional"))
    )
    (net (code "68") (name "Net-(U$28-PadP$4)") (class "Default")
      (node (ref "U$28") (pin "P$4") (pinfunction "P$4_P$4") (pintype "bidirectional"))
      (node (ref "U$3") (pin "D") (pinfunction "D_D") (pintype "bidirectional"))
    )
    (net (code "69") (name "Net-(U$28-PadP$5)") (class "Default")
      (node (ref "U$28") (pin "P$5") (pinfunction "P$5_P$5") (pintype "bidirectional"))
      (node (ref "U$4") (pin "D") (pinfunction "D_D") (pintype "bidirectional"))
    )
    (net (code "70") (name "Net-(U$28-PadP$6)") (class "Default")
      (node (ref "U$28") (pin "P$6") (pinfunction "P$6_P$6") (pintype "bidirectional"))
      (node (ref "U$5") (pin "D") (pinfunction "D_D") (pintype "bidirectional"))
    )
    (net (code "71") (name "Net-(U$28-PadP$7)") (class "Default")
      (node (ref "U$28") (pin "P$7") (pinfunction "P$7_P$7") (pintype "bidirectional"))
      (node (ref "U$6") (pin "D") (pinfunction "D_D") (pintype "bidirectional"))
    )
    (net (code "72") (name "Net-(U$28-PadP$8)") (class "Default")
      (node (ref "U$28") (pin "P$8") (pinfunction "P$8_P$8") (pintype "bidirectional"))
      (node (ref "U$7") (pin "D") (pinfunction "D_D") (pintype "bidirectional"))
    )
    (net (code "73") (name "Net-(U$29-P+)") (class "Default")
      (node (ref "U$19") (pin "P$4") (pinfunction "P$4_P$4") (pintype "bidirectional"))
      (node (ref "U$20") (pin "P$4") (pinfunction "P$4_P$4") (pintype "bidirectional"))
      (node (ref "U$21") (pin "P$4") (pinfunction "P$4_P$4") (pintype "bidirectional"))
      (node (ref "U$22") (pin "P$4") (pinfunction "P$4_P$4") (pintype "bidirectional"))
      (node (ref "U$27") (pin "P$10") (pinfunction "P$10_P$10") (pintype "bidirectional"))
      (node (ref "U$27") (pin "P$11") (pinfunction "P$11_P$11") (pintype "bidirectional"))
      (node (ref "U$27") (pin "P$12") (pinfunction "P$12_P$12") (pintype "bidirectional"))
      (node (ref "U$27") (pin "P$13") (pinfunction "P$13_P$13") (pintype "bidirectional"))
      (node (ref "U$27") (pin "P$14") (pinfunction "P$14_P$14") (pintype "bidirectional"))
      (node (ref "U$27") (pin "P$15") (pinfunction "P$15_P$15") (pintype "bidirectional"))
      (node (ref "U$27") (pin "P$16") (pinfunction "P$16_P$16") (pintype "bidirectional"))
      (node (ref "U$27") (pin "P$9") (pinfunction "P$9_P$9") (pintype "bidirectional"))
      (node (ref "U$28") (pin "P$10") (pinfunction "P$10_P$10") (pintype "bidirectional"))
      (node (ref "U$28") (pin "P$11") (pinfunction "P$11_P$11") (pintype "bidirectional"))
      (node (ref "U$28") (pin "P$12") (pinfunction "P$12_P$12") (pintype "bidirectional"))
      (node (ref "U$28") (pin "P$13") (pinfunction "P$13_P$13") (pintype "bidirectional"))
      (node (ref "U$28") (pin "P$14") (pinfunction "P$14_P$14") (pintype "bidirectional"))
      (node (ref "U$28") (pin "P$15") (pinfunction "P$15_P$15") (pintype "bidirectional"))
      (node (ref "U$28") (pin "P$16") (pinfunction "P$16_P$16") (pintype "bidirectional"))
      (node (ref "U$28") (pin "P$9") (pinfunction "P$9_P$9") (pintype "bidirectional"))
      (node (ref "U$29") (pin "P$2") (pinfunction "P+_P$2") (pintype "bidirectional"))
      (node (ref "U$31") (pin "P$1") (pinfunction "P$1_P$1") (pintype "bidirectional"))
      (node (ref "U$32") (pin "VMOT") (pinfunction "VMOT_VMOT") (pintype "bidirectional"))
      (node (ref "U$35") (pin "P$3") (pinfunction "P$3_P$3") (pintype "bidirectional"))
      (node (ref "U$35") (pin "P$4") (pinfunction "P$4_P$4") (pintype "bidirectional"))
      (node (ref "U$39") (pin "VIN") (pinfunction "VIN_VIN") (pintype "bidirectional"))
      (node (ref "U$40") (pin "P$3") (pinfunction "P$3_P$3") (pintype "bidirectional"))
      (node (ref "U$40") (pin "P$4") (pinfunction "P$4_P$4") (pintype "bidirectional"))
      (node (ref "U$41") (pin "P$3") (pinfunction "P$3_P$3") (pintype "bidirectional"))
      (node (ref "U$41") (pin "P$4") (pinfunction "P$4_P$4") (pintype "bidirectional"))
    )
    (net (code "74") (name "Net-(U$30-PadP$1)") (class "Default")
      (node (ref "U$30") (pin "P$1") (pinfunction "P$1_P$1") (pintype "bidirectional"))
      (node (ref "U$32") (pin "B2") (pinfunction "B2_B2") (pintype "bidirectional"))
    )
    (net (code "75") (name "Net-(U$30-PadP$2)") (class "Default")
      (node (ref "U$30") (pin "P$2") (pinfunction "P$2_P$2") (pintype "bidirectional"))
      (node (ref "U$32") (pin "B1") (pinfunction "B1_B1") (pintype "bidirectional"))
    )
    (net (code "76") (name "Net-(U$30-PadP$3)") (class "Default")
      (node (ref "U$30") (pin "P$3") (pinfunction "P$3_P$3") (pintype "bidirectional"))
      (node (ref "U$32") (pin "A1") (pinfunction "A1_A1") (pintype "bidirectional"))
    )
    (net (code "77") (name "Net-(U$30-PadP$4)") (class "Default")
      (node (ref "U$30") (pin "P$4") (pinfunction "P$4_P$4") (pintype "bidirectional"))
      (node (ref "U$32") (pin "A2") (pinfunction "A2_A2") (pintype "bidirectional"))
    )
    (net (code "78") (name "Net-(U$31-PadP$2)") (class "Default")
      (node (ref "U$31") (pin "P$2") (pinfunction "P$2_P$2") (pintype "bidirectional"))
      (node (ref "U$38") (pin "P$4") (pinfunction "P$4_P$4") (pintype "bidirectional"))
      (node (ref "U$38") (pin "P$6") (pinfunction "P$6_P$6") (pintype "bidirectional"))
    )
    (net (code "79") (name "Net-(U$33-PadD)") (class "Default")
      (node (ref "U$33") (pin "D") (pinfunction "D_D") (pintype "bidirectional"))
      (node (ref "U$35") (pin "P$2") (pinfunction "P$2_P$2") (pintype "bidirectional"))
    )
    (net (code "80") (name "Net-(U$34-PadD)") (class "Default")
      (node (ref "U$34") (pin "D") (pinfunction "D_D") (pintype "bidirectional"))
      (node (ref "U$35") (pin "P$1") (pinfunction "P$1_P$1") (pintype "bidirectional"))
    )
    (net (code "81") (name "Net-(U$40-PadP$1)") (class "Default")
      (node (ref "U$40") (pin "P$1") (pinfunction "P$1_P$1") (pintype "bidirectional"))
      (node (ref "U$43") (pin "D") (pinfunction "D_D") (pintype "bidirectional"))
    )
    (net (code "82") (name "Net-(U$40-PadP$2)") (class "Default")
      (node (ref "U$40") (pin "P$2") (pinfunction "P$2_P$2") (pintype "bidirectional"))
      (node (ref "U$42") (pin "D") (pinfunction "D_D") (pintype "bidirectional"))
    )
    (net (code "83") (name "Net-(U$41-PadP$1)") (class "Default")
      (node (ref "U$41") (pin "P$1") (pinfunction "P$1_P$1") (pintype "bidirectional"))
      (node (ref "U$45") (pin "D") (pinfunction "D_D") (pintype "bidirectional"))
    )
    (net (code "84") (name "Net-(U$41-PadP$2)") (class "Default")
      (node (ref "U$41") (pin "P$2") (pinfunction "P$2_P$2") (pintype "bidirectional"))
      (node (ref "U$44") (pin "D") (pinfunction "D_D") (pintype "bidirectional"))
    )
    (net (code "85") (name "Net-(U$50-P$4)") (class "Default")
      (node (ref "U$1") (pin "CLK") (pinfunction "CLK_CLK") (pintype "bidirectional"))
      (node (ref "U$23") (pin "CLK") (pinfunction "CLK_CLK") (pintype "bidirectional"))
      (node (ref "U$24") (pin "Y6") (pinfunction "Y6_Y6") (pintype "bidirectional"))
      (node (ref "U$25") (pin "CLK") (pinfunction "CLK_CLK") (pintype "bidirectional"))
      (node (ref "U$26") (pin "CLK") (pinfunction "CLK_CLK") (pintype "bidirectional"))
      (node (ref "U$50") (pin "SCK") (pinfunction "P$4_SCK") (pintype "bidirectional"))
      (node (ref "U$51") (pin "SCK") (pinfunction "P$4_SCK") (pintype "bidirectional"))
      (node (ref "U$52") (pin "SCK") (pinfunction "P$4_SCK") (pintype "bidirectional"))
      (node (ref "U$53") (pin "SCK") (pinfunction "P$4_SCK") (pintype "bidirectional"))
    )
    (net (code "86") (name "unconnected-(U$1-Pad3V3)") (class "Default")
      (node (ref "U$1") (pin "3V3") (pinfunction "3V3_3V3") (pintype "bidirectional"))
    )
    (net (code "87") (name "unconnected-(U$1-PadRDY)") (class "Default")
      (node (ref "U$1") (pin "RDY") (pinfunction "RDY_RDY") (pintype "bidirectional"))
    )
    (net (code "88") (name "unconnected-(U$10-PadITA)") (class "Default")
      (node (ref "U$10") (pin "ITA") (pinfunction "ITA_ITA") (pintype "bidirectional"))
    )
    (net (code "89") (name "unconnected-(U$10-PadITB)") (class "Default")
      (node (ref "U$10") (pin "ITB") (pinfunction "ITB_ITB") (pintype "bidirectional"))
    )
    (net (code "90") (name "unconnected-(U$10-PadNC_CS)") (class "Default")
      (node (ref "U$10") (pin "NC_CS") (pinfunction "NC_CS_NC_CS") (pintype "bidirectional"))
    )
    (net (code "91") (name "unconnected-(U$10-PadNC_SO)") (class "Default")
      (node (ref "U$10") (pin "NC_SO") (pinfunction "NC_SO_NC_SO") (pintype "bidirectional"))
    )
    (net (code "92") (name "unconnected-(U$10-PadRESET)") (class "Default")
      (node (ref "U$10") (pin "RESET") (pinfunction "RESET_RESET") (pintype "bidirectional"))
    )
    (net (code "93") (name "unconnected-(U$10-PadVCC_2)") (class "Default")
      (node (ref "U$10") (pin "VCC_2") (pinfunction "VCC_2_VCC_2") (pintype "bidirectional"))
    )
    (net (code "94") (name "unconnected-(U$19-PadP$1)") (class "Default")
      (node (ref "U$19") (pin "P$1") (pinfunction "P$1_P$1") (pintype "bidirectional"))
    )
    (net (code "95") (name "unconnected-(U$19-PadP$6)") (class "Default")
      (node (ref "U$19") (pin "P$6") (pinfunction "P$6_P$6") (pintype "bidirectional"))
    )
    (net (code "96") (name "unconnected-(U$19-PadP$7)") (class "Default")
      (node (ref "U$19") (pin "P$7") (pinfunction "P$7_P$7") (pintype "bidirectional"))
    )
    (net (code "97") (name "unconnected-(U$19-PadP$8)") (class "Default")
      (node (ref "U$19") (pin "P$8") (pinfunction "P$8_P$8") (pintype "bidirectional"))
    )
    (net (code "98") (name "unconnected-(U$19-PadP$9)") (class "Default")
      (node (ref "U$19") (pin "P$9") (pinfunction "P$9_P$9") (pintype "bidirectional"))
    )
    (net (code "99") (name "unconnected-(U$20-PadP$1)") (class "Default")
      (node (ref "U$20") (pin "P$1") (pinfunction "P$1_P$1") (pintype "bidirectional"))
    )
    (net (code "100") (name "unconnected-(U$20-PadP$6)") (class "Default")
      (node (ref "U$20") (pin "P$6") (pinfunction "P$6_P$6") (pintype "bidirectional"))
    )
    (net (code "101") (name "unconnected-(U$20-PadP$7)") (class "Default")
      (node (ref "U$20") (pin "P$7") (pinfunction "P$7_P$7") (pintype "bidirectional"))
    )
    (net (code "102") (name "unconnected-(U$20-PadP$8)") (class "Default")
      (node (ref "U$20") (pin "P$8") (pinfunction "P$8_P$8") (pintype "bidirectional"))
    )
    (net (code "103") (name "unconnected-(U$20-PadP$9)") (class "Default")
      (node (ref "U$20") (pin "P$9") (pinfunction "P$9_P$9") (pintype "bidirectional"))
    )
    (net (code "104") (name "unconnected-(U$21-PadP$1)") (class "Default")
      (node (ref "U$21") (pin "P$1") (pinfunction "P$1_P$1") (pintype "bidirectional"))
    )
    (net (code "105") (name "unconnected-(U$21-PadP$6)") (class "Default")
      (node (ref "U$21") (pin "P$6") (pinfunction "P$6_P$6") (pintype "bidirectional"))
    )
    (net (code "106") (name "unconnected-(U$21-PadP$7)") (class "Default")
      (node (ref "U$21") (pin "P$7") (pinfunction "P$7_P$7") (pintype "bidirectional"))
    )
    (net (code "107") (name "unconnected-(U$21-PadP$8)") (class "Default")
      (node (ref "U$21") (pin "P$8") (pinfunction "P$8_P$8") (pintype "bidirectional"))
    )
    (net (code "108") (name "unconnected-(U$21-PadP$9)") (class "Default")
      (node (ref "U$21") (pin "P$9") (pinfunction "P$9_P$9") (pintype "bidirectional"))
    )
    (net (code "109") (name "unconnected-(U$22-PadP$1)") (class "Default")
      (node (ref "U$22") (pin "P$1") (pinfunction "P$1_P$1") (pintype "bidirectional"))
    )
    (net (code "110") (name "unconnected-(U$22-PadP$6)") (class "Default")
      (node (ref "U$22") (pin "P$6") (pinfunction "P$6_P$6") (pintype "bidirectional"))
    )
    (net (code "111") (name "unconnected-(U$22-PadP$7)") (class "Default")
      (node (ref "U$22") (pin "P$7") (pinfunction "P$7_P$7") (pintype "bidirectional"))
    )
    (net (code "112") (name "unconnected-(U$22-PadP$8)") (class "Default")
      (node (ref "U$22") (pin "P$8") (pinfunction "P$8_P$8") (pintype "bidirectional"))
    )
    (net (code "113") (name "unconnected-(U$22-PadP$9)") (class "Default")
      (node (ref "U$22") (pin "P$9") (pinfunction "P$9_P$9") (pintype "bidirectional"))
    )
    (net (code "114") (name "unconnected-(U$23-Pad3V3)") (class "Default")
      (node (ref "U$23") (pin "3V3") (pinfunction "3V3_3V3") (pintype "bidirectional"))
    )
    (net (code "115") (name "unconnected-(U$23-PadRDY)") (class "Default")
      (node (ref "U$23") (pin "RDY") (pinfunction "RDY_RDY") (pintype "bidirectional"))
    )
    (net (code "116") (name "unconnected-(U$24-PadA3V3)") (class "Default")
      (node (ref "U$24") (pin "A3V3") (pinfunction "A3V3_A3V3") (pintype "bidirectional"))
    )
    (net (code "117") (name "unconnected-(U$24-PadAGND)") (class "Default")
      (node (ref "U$24") (pin "AGND") (pinfunction "AGND_AGND") (pintype "bidirectional"))
    )
    (net (code "118") (name "unconnected-(U$24-PadBOOT0)") (class "Default")
      (node (ref "U$24") (pin "BOOT0") (pinfunction "BOOT0_BOOT0") (pintype "bidirectional"))
    )
    (net (code "119") (name "unconnected-(U$24-PadP2)") (class "Default")
      (node (ref "U$24") (pin "P2") (pinfunction "P2_P2") (pintype "bidirectional"))
    )
    (net (code "120") (name "unconnected-(U$24-PadP3)") (class "Default")
      (node (ref "U$24") (pin "P3") (pinfunction "P3_P3") (pintype "bidirectional"))
    )
    (net (code "121") (name "unconnected-(U$24-PadP4)") (class "Default")
      (node (ref "U$24") (pin "P4") (pinfunction "P4_P4") (pintype "bidirectional"))
    )
    (net (code "122") (name "unconnected-(U$24-PadP5)") (class "Default")
      (node (ref "U$24") (pin "P5") (pinfunction "P5_P5") (pintype "bidirectional"))
    )
    (net (code "123") (name "unconnected-(U$24-PadRSTX)") (class "Default")
      (node (ref "U$24") (pin "RSTX") (pinfunction "RSTX_RSTX") (pintype "bidirectional"))
    )
    (net (code "124") (name "unconnected-(U$24-PadRSTY)") (class "Default")
      (node (ref "U$24") (pin "RSTY") (pinfunction "RSTY_RSTY") (pintype "bidirectional"))
    )
    (net (code "125") (name "unconnected-(U$24-PadV+A)") (class "Default")
      (node (ref "U$24") (pin "V+A") (pinfunction "V+A_V+A") (pintype "bidirectional"))
    )
    (net (code "126") (name "unconnected-(U$24-PadV+B)") (class "Default")
      (node (ref "U$24") (pin "V+B") (pinfunction "V+B_V+B") (pintype "bidirectional"))
    )
    (net (code "127") (name "unconnected-(U$24-PadV+C)") (class "Default")
      (node (ref "U$24") (pin "V+C") (pinfunction "V+C_V+C") (pintype "bidirectional"))
    )
    (net (code "128") (name "unconnected-(U$24-PadV+D)") (class "Default")
      (node (ref "U$24") (pin "V+D") (pinfunction "V+D_V+D") (pintype "bidirectional"))
    )
    (net (code "129") (name "unconnected-(U$24-PadV+E)") (class "Default")
      (node (ref "U$24") (pin "V+E") (pinfunction "V+E_V+E") (pintype "bidirectional"))
    )
    (net (code "130") (name "unconnected-(U$24-PadV+X)") (class "Default")
      (node (ref "U$24") (pin "V+X") (pinfunction "V+X_V+X") (pintype "bidirectional"))
    )
    (net (code "131") (name "unconnected-(U$24-PadVBACK)") (class "Default")
      (node (ref "U$24") (pin "VBACK") (pinfunction "VBACK_VBACK") (pintype "bidirectional"))
    )
    (net (code "132") (name "unconnected-(U$24-PadY5)") (class "Default")
      (node (ref "U$24") (pin "Y5") (pinfunction "Y5_Y5") (pintype "bidirectional"))
    )
    (net (code "133") (name "unconnected-(U$25-Pad3V3)") (class "Default")
      (node (ref "U$25") (pin "3V3") (pinfunction "3V3_3V3") (pintype "bidirectional"))
    )
    (net (code "134") (name "unconnected-(U$25-PadRDY)") (class "Default")
      (node (ref "U$25") (pin "RDY") (pinfunction "RDY_RDY") (pintype "bidirectional"))
    )
    (net (code "135") (name "unconnected-(U$26-Pad3V3)") (class "Default")
      (node (ref "U$26") (pin "3V3") (pinfunction "3V3_3V3") (pintype "bidirectional"))
    )
    (net (code "136") (name "unconnected-(U$26-PadRDY)") (class "Default")
      (node (ref "U$26") (pin "RDY") (pinfunction "RDY_RDY") (pintype "bidirectional"))
    )
    (net (code "137") (name "unconnected-(U$32-PadEN)") (class "Default")
      (node (ref "U$32") (pin "EN") (pinfunction "EN_EN") (pintype "bidirectional"))
    )
    (net (code "138") (name "unconnected-(U$32-PadFLT)") (class "Default")
      (node (ref "U$32") (pin "FLT") (pinfunction "FLT_FLT") (pintype "bidirectional"))
    )
    (net (code "139") (name "unconnected-(U$32-PadI1)") (class "Default")
      (node (ref "U$32") (pin "I1") (pinfunction "I1_I1") (pintype "bidirectional"))
    )
    (net (code "140") (name "unconnected-(U$32-PadI2)") (class "Default")
      (node (ref "U$32") (pin "I2") (pinfunction "I2_I2") (pintype "bidirectional"))
    )
    (net (code "141") (name "unconnected-(U$38-PadP$2)") (class "Default")
      (node (ref "U$38") (pin "P$2") (pinfunction "P$2_P$2") (pintype "bidirectional"))
    )
    (net (code "142") (name "unconnected-(U$38-PadP$5)") (class "Default")
      (node (ref "U$38") (pin "P$5") (pinfunction "P$5_P$5") (pintype "bidirectional"))
    )
    (net (code "143") (name "unconnected-(U$39-PadEN)") (class "Default")
      (node (ref "U$39") (pin "EN") (pinfunction "EN_EN") (pintype "bidirectional"))
    )
    (net (code "144") (name "unconnected-(U$49-PadP$3)") (class "Default")
      (node (ref "U$49") (pin "P$3") (pinfunction "P$3_P$3") (pintype "bidirectional"))
    )
    (net (code "145") (name "unconnected-(U$49-PadP$4)") (class "Default")
      (node (ref "U$49") (pin "P$4") (pinfunction "P$4_P$4") (pintype "bidirectional"))
    )
    (net (code "146") (name "unconnected-(U$50-Pad3VO)") (class "Default")
      (node (ref "U$50") (pin "3VO") (pinfunction "3VO_3VO") (pintype "bidirectional"))
    )
    (net (code "147") (name "unconnected-(U$50-PadDRDY)") (class "Default")
      (node (ref "U$50") (pin "DRDY") (pinfunction "DRDY_DRDY") (pintype "bidirectional"))
    )
    (net (code "148") (name "unconnected-(U$50-PadFLT)") (class "Default")
      (node (ref "U$50") (pin "FLT") (pinfunction "FLT_FLT") (pintype "bidirectional"))
    )
    (net (code "149") (name "unconnected-(U$51-Pad3VO)") (class "Default")
      (node (ref "U$51") (pin "3VO") (pinfunction "3VO_3VO") (pintype "bidirectional"))
    )
    (net (code "150") (name "unconnected-(U$51-PadDRDY)") (class "Default")
      (node (ref "U$51") (pin "DRDY") (pinfunction "DRDY_DRDY") (pintype "bidirectional"))
    )
    (net (code "151") (name "unconnected-(U$51-PadFLT)") (class "Default")
      (node (ref "U$51") (pin "FLT") (pinfunction "FLT_FLT") (pintype "bidirectional"))
    )
    (net (code "152") (name "unconnected-(U$52-Pad3VO)") (class "Default")
      (node (ref "U$52") (pin "3VO") (pinfunction "3VO_3VO") (pintype "bidirectional"))
    )
    (net (code "153") (name "unconnected-(U$52-PadDRDY)") (class "Default")
      (node (ref "U$52") (pin "DRDY") (pinfunction "DRDY_DRDY") (pintype "bidirectional"))
    )
    (net (code "154") (name "unconnected-(U$52-PadFLT)") (class "Default")
      (node (ref "U$52") (pin "FLT") (pinfunction "FLT_FLT") (pintype "bidirectional"))
    )
    (net (code "155") (name "unconnected-(U$53-Pad3VO)") (class "Default")
      (node (ref "U$53") (pin "3VO") (pinfunction "3VO_3VO") (pintype "bidirectional"))
    )
    (net (code "156") (name "unconnected-(U$53-PadDRDY)") (class "Default")
      (node (ref "U$53") (pin "DRDY") (pinfunction "DRDY_DRDY") (pintype "bidirectional"))
    )
    (net (code "157") (name "unconnected-(U$53-PadFLT)") (class "Default")
      (node (ref "U$53") (pin "FLT") (pinfunction "FLT_FLT") (pintype "bidirectional"))
    )
    (net (code "158") (name "unconnected-(U$54-PadP1)") (class "Default")
      (node (ref "U$54") (pin "P1") (pinfunction "P1_P1") (pintype "bidirectional"))
    )
    (net (code "159") (name "unconnected-(U$54-PadP2)") (class "Default")
      (node (ref "U$54") (pin "P2") (pinfunction "P2_P2") (pintype "bidirectional"))
    )
    (net (code "160") (name "unconnected-(U$54-PadP3)") (class "Default")
      (node (ref "U$54") (pin "P3") (pinfunction "P3_P3") (pintype "bidirectional"))
    )
    (net (code "161") (name "unconnected-(U$54-PadP4)") (class "Default")
      (node (ref "U$54") (pin "P4") (pinfunction "P4_P4") (pintype "bidirectional"))
    )
    (net (code "162") (name "unconnected-(U$54-PadP5)") (class "Default")
      (node (ref "U$54") (pin "P5") (pinfunction "P5_P5") (pintype "bidirectional"))
    )
    (net (code "163") (name "unconnected-(U$54-PadP6)") (class "Default")
      (node (ref "U$54") (pin "P6") (pinfunction "P6_P6") (pintype "bidirectional"))
    )
    (net (code "164") (name "unconnected-(U$55-PadP1)") (class "Default")
      (node (ref "U$55") (pin "P1") (pinfunction "P1_P1") (pintype "bidirectional"))
    )
    (net (code "165") (name "unconnected-(U$55-PadP2)") (class "Default")
      (node (ref "U$55") (pin "P2") (pinfunction "P2_P2") (pintype "bidirectional"))
    )
    (net (code "166") (name "unconnected-(U$55-PadP3)") (class "Default")
      (node (ref "U$55") (pin "P3") (pinfunction "P3_P3") (pintype "bidirectional"))
    )
    (net (code "167") (name "unconnected-(U$55-PadP4)") (class "Default")
      (node (ref "U$55") (pin "P4") (pinfunction "P4_P4") (pintype "bidirectional"))
    )
    (net (code "168") (name "unconnected-(U$55-PadP5)") (class "Default")
      (node (ref "U$55") (pin "P5") (pinfunction "P5_P5") (pintype "bidirectional"))
    )
    (net (code "169") (name "unconnected-(U$55-PadP6)") (class "Default")
      (node (ref "U$55") (pin "P6") (pinfunction "P6_P6") (pintype "bidirectional"))
    )
  )
)
